# Power_Board_DRV8323.net
KiCad netlist of a schematic drawn in Altium Designer
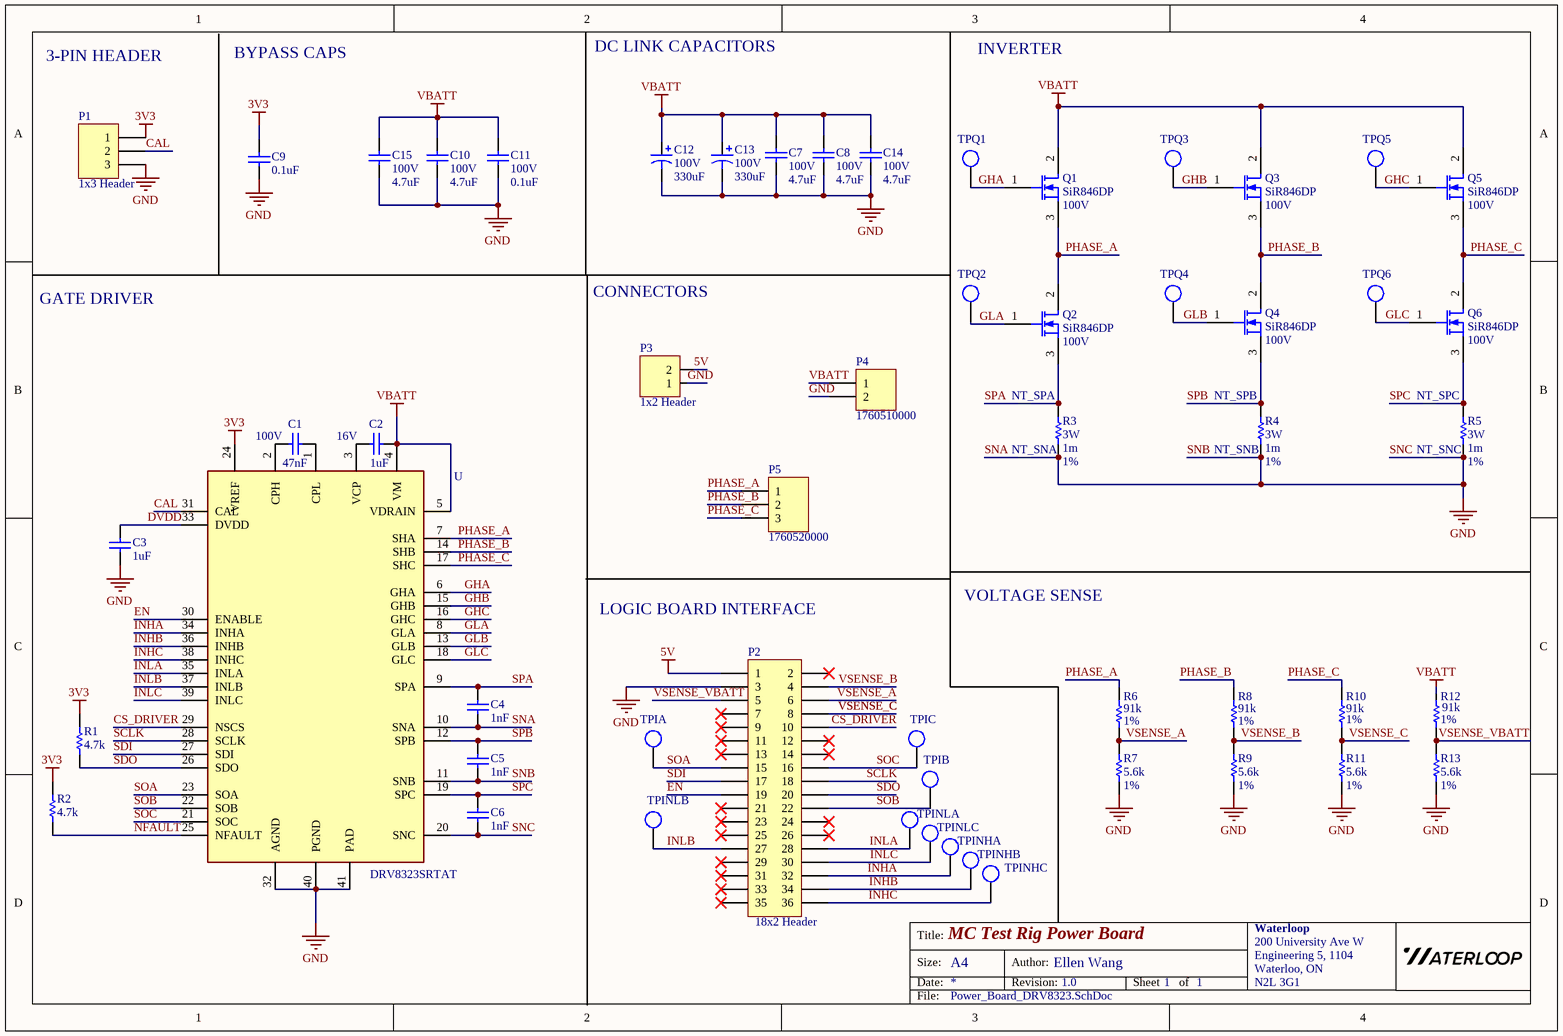
[diagram p0: Power_Board_DRV8323.SchDoc]

(export (version "E")
  (design (tool "Eeschema 10.0.6"))
  (components
    (comp (ref "C1")
      (value "47nF")
      (footprint "0805 - Capacitor")
      (description "Nonpolarized Capacitor")
      (fields
        (field (name "MANUFACTURER") "YAGEO")
        (field (name "RATING") "100V")
        (field (name "MANUFACTURER PART NUMBER") "CC0805KKX7R0BB473")
      )
      (libsource (lib "General") (part "Capacitor - Nonpolarized"))
    )
    (comp (ref "C2")
      (value "1uF")
      (footprint "0805 - Capacitor")
      (description "Nonpolarized Capacitor")
      (fields
        (field (name "MANUFACTURER") "YAGEO")
        (field (name "RATING") "16V")
        (field (name "MANUFACTURER PART NUMBER") "CC0805KKX7R7BB105")
      )
      (libsource (lib "General") (part "Capacitor - Nonpolarized"))
    )
    (comp (ref "C3")
      (value "1uF")
      (footprint "0805 - Capacitor")
      (description "Nonpolarized Capacitor")
      (fields
        (field (name "MANUFACTURER") "YAGEO")
        (field (name "MANUFACTURER PART NUMBER") "CC0805KKX7R7BB105")
      )
      (libsource (lib "General") (part "Capacitor - Nonpolarized"))
    )
    (comp (ref "C4")
      (value "1nF")
      (footprint "0805 - Capacitor")
      (description "Nonpolarized Capacitor")
      (fields
        (field (name "MANUFACTURER") "YAGEO")
        (field (name "MANUFACTURER PART NUMBER") "CC0805KRX7R0BB102")
      )
      (libsource (lib "General") (part "Capacitor - Nonpolarized"))
    )
    (comp (ref "C5")
      (value "1nF")
      (footprint "0805 - Capacitor")
      (description "Nonpolarized Capacitor")
      (fields
        (field (name "MANUFACTURER") "YAGEO")
        (field (name "MANUFACTURER PART NUMBER") "CC0805KRX7R0BB102")
      )
      (libsource (lib "General") (part "Capacitor - Nonpolarized"))
    )
    (comp (ref "C6")
      (value "1nF")
      (footprint "0805 - Capacitor")
      (description "Nonpolarized Capacitor")
      (fields
        (field (name "MANUFACTURER") "YAGEO")
        (field (name "MANUFACTURER PART NUMBER") "CC0805KRX7R0BB102")
      )
      (libsource (lib "General") (part "Capacitor - Nonpolarized"))
    )
    (comp (ref "C7")
      (value "4.7uF")
      (footprint "1210 - Capacitor")
      (description "Nonpolarized Capacitor")
      (fields
        (field (name "MANUFACTURER") "Holy Stone Enterprise Co., Ltd.")
        (field (name "RATING") "100V")
        (field (name "MANUFACTURER PART NUMBER") "C1210X475K101T")
      )
      (libsource (lib "General") (part "Capacitor - Nonpolarized"))
    )
    (comp (ref "C8")
      (value "4.7uF")
      (footprint "1210 - Capacitor")
      (description "Nonpolarized Capacitor")
      (fields
        (field (name "MANUFACTURER") "Holy Stone Enterprise Co., Ltd.")
        (field (name "RATING") "100V")
        (field (name "MANUFACTURER PART NUMBER") "C1210X475K101T")
      )
      (libsource (lib "") (part "Capacitor - Nonpolarized_2"))
    )
    (comp (ref "C9")
      (value "0.1uF")
      (footprint "0805 - Capacitor")
      (description "Nonpolarized Capacitor")
      (fields
        (field (name "MANUFACTURER") "Samsung Electro-Mechanics")
        (field (name "MANUFACTURER PART NUMBER") "CL21B104KCFWPNE")
      )
      (libsource (lib "") (part "Capacitor - Nonpolarized_1"))
    )
    (comp (ref "C10")
      (value "4.7uF")
      (footprint "1210 - Capacitor")
      (description "Nonpolarized Capacitor")
      (fields
        (field (name "MANUFACTURER") "Holy Stone Enterprise Co., Ltd.")
        (field (name "RATING") "100V")
        (field (name "MANUFACTURER PART NUMBER") "C1210X475K101T")
      )
      (libsource (lib "") (part "Capacitor - Nonpolarized_2"))
    )
    (comp (ref "C11")
      (value "0.1uF")
      (footprint "0805 - Capacitor")
      (description "Nonpolarized Capacitor")
      (fields
        (field (name "MANUFACTURER") "Samsung Electro-Mechanics")
        (field (name "RATING") "100V")
        (field (name "MANUFACTURER PART NUMBER") "CL21B104KCFWPNE")
      )
      (libsource (lib "") (part "Capacitor - Nonpolarized_2"))
    )
    (comp (ref "C12")
      (value "330uF")
      (footprint "OCVZ0606 - CAPACITOR")
      (description "Polarized Capacitor")
      (fields
        (field (name "RATING") "100V")
        (field (name "MANUFACTURER") "Panasonic Electronic Components")
        (field (name "MANUFACTURER PART NUMBER") "EEE-FK2A331AM")
      )
      (libsource (lib "General") (part "Capacitor - Polarized"))
    )
    (comp (ref "C13")
      (value "330uF")
      (footprint "OCVZ0606 - CAPACITOR")
      (description "Polarized Capacitor")
      (fields
        (field (name "RATING") "100V")
        (field (name "MANUFACTURER") "Panasonic Electronic Components")
        (field (name "MANUFACTURER PART NUMBER") "EEE-FK2A331AM")
      )
      (libsource (lib "General") (part "Capacitor - Polarized"))
    )
    (comp (ref "C14")
      (value "4.7uF")
      (footprint "1210 - Capacitor")
      (description "Nonpolarized Capacitor")
      (fields
        (field (name "MANUFACTURER") "Holy Stone Enterprise Co., Ltd.")
        (field (name "RATING") "100V")
        (field (name "MANUFACTURER PART NUMBER") "C1210X475K101T")
      )
      (libsource (lib "") (part "Capacitor - Nonpolarized_2"))
    )
    (comp (ref "C15")
      (value "4.7uF")
      (footprint "1210 - Capacitor")
      (description "Nonpolarized Capacitor")
      (fields
        (field (name "MANUFACTURER") "Holy Stone Enterprise Co., Ltd.")
        (field (name "RATING") "100V")
        (field (name "MANUFACTURER PART NUMBER") "C1210X475K101T")
      )
      (libsource (lib "") (part "Capacitor - Nonpolarized_2"))
    )
    (comp (ref "NT_SNA") (value "NetTie") (footprint "Net Tie") (libsource (lib "General") (part "Net Tie")))
    (comp (ref "NT_SNB") (value "NetTie") (footprint "Net Tie") (libsource (lib "General") (part "Net Tie")))
    (comp (ref "NT_SNC") (value "NetTie") (footprint "Net Tie") (libsource (lib "General") (part "Net Tie")))
    (comp (ref "NT_SPA") (value "NetTie") (footprint "Net Tie") (libsource (lib "General") (part "Net Tie")))
    (comp (ref "NT_SPB") (value "NetTie") (footprint "Net Tie") (libsource (lib "General") (part "Net Tie")))
    (comp (ref "NT_SPC") (value "NetTie") (footprint "Net Tie") (libsource (lib "General") (part "Net Tie")))
    (comp (ref "P1")
      (value "1x3 Header")
      (footprint "HDR1X3")
      (description "1x3 Pin Header")
      (libsource (lib "GeneralConnectors") (part "1x3 Header"))
    )
    (comp (ref "P2")
      (value "Header 18X2")
      (footprint "HDR2X18")
      (description "Header, 18-Pin, Dual row")
      (fields (field (name "PUBLISHER") "Altium Limited"))
      (libsource (lib "Miscellaneous Connectors") (part "Header 18X2"))
    )
    (comp (ref "P3")
      (value "1x2 Header")
      (footprint "HDR1X2")
      (description "1x2 Pin Header")
      (libsource (lib "GeneralConnectors") (part "1x2 Header"))
    )
    (comp (ref "P4")
      (value "1760510000")
      (footprint "1760510000")
      (description "1x2 Screw Terminal Block")
      (fields
        (field (name "MANUFACTURER PART NUMBER") "OSTTC022162")
        (field (name "MANUFACTURER") "On Shore Technology Inc.")
      )
      (libsource (lib "GeneralConnectors") (part "1760510000"))
    )
    (comp (ref "P5")
      (value "1760520000")
      (footprint "1760520000")
      (description "1x3 Screw Terminal Block")
      (fields
        (field (name "MANUFACTURER PART NUMBER") "282857-3")
        (field (name "MANUFACTURER") "TE Connectivity AMP Connectors")
      )
      (libsource (lib "GeneralConnectors") (part "1760520000"))
    )
    (comp (ref "Q1")
      (value "MOSFET-N")
      (footprint "PowerPAK® SO-8")
      (description "N-Channel MOSFET")
      (fields (field (name "SUPPLIER PART NUMBER") "SiR846DP") (field (name "RATING") "100V"))
      (libsource (lib "General") (part "MOSFET-N"))
    )
    (comp (ref "Q2")
      (value "MOSFET-N")
      (footprint "PowerPAK® SO-8")
      (description "N-Channel MOSFET")
      (fields (field (name "SUPPLIER PART NUMBER") "SiR846DP") (field (name "RATING") "100V"))
      (libsource (lib "General") (part "MOSFET-N"))
    )
    (comp (ref "Q3")
      (value "MOSFET-N")
      (footprint "PowerPAK® SO-8")
      (description "N-Channel MOSFET")
      (fields (field (name "SUPPLIER PART NUMBER") "SiR846DP") (field (name "RATING") "100V"))
      (libsource (lib "General") (part "MOSFET-N"))
    )
    (comp (ref "Q4")
      (value "MOSFET-N")
      (footprint "PowerPAK® SO-8")
      (description "N-Channel MOSFET")
      (fields (field (name "SUPPLIER PART NUMBER") "SiR846DP") (field (name "RATING") "100V"))
      (libsource (lib "General") (part "MOSFET-N"))
    )
    (comp (ref "Q5")
      (value "MOSFET-N")
      (footprint "PowerPAK® SO-8")
      (description "N-Channel MOSFET")
      (fields (field (name "SUPPLIER PART NUMBER") "SiR846DP") (field (name "RATING") "100V"))
      (libsource (lib "General") (part "MOSFET-N"))
    )
    (comp (ref "Q6")
      (value "MOSFET-N")
      (footprint "PowerPAK® SO-8")
      (description "N-Channel MOSFET")
      (fields (field (name "SUPPLIER PART NUMBER") "SiR846DP") (field (name "RATING") "100V"))
      (libsource (lib "General") (part "MOSFET-N"))
    )
    (comp (ref "R1")
      (value "4.7k")
      (footprint "0603 - Resistor")
      (description "Resistor")
      (fields
        (field (name "MANUFACTURER PART NUMBER") "RC0603FR-074K7L")
        (field (name "MANUFACTURER") "YAGEO")
      )
      (libsource (lib "General") (part "Resistor"))
    )
    (comp (ref "R2")
      (value "4.7k")
      (footprint "0603 - Resistor")
      (description "Resistor")
      (fields
        (field (name "MANUFACTURER PART NUMBER") "RC0603FR-074K7L")
        (field (name "MANUFACTURER") "YAGEO")
      )
      (libsource (lib "General") (part "Resistor"))
    )
    (comp (ref "R3")
      (value "1m")
      (footprint "2512 - RESISTOR")
      (description "Resistor")
      (fields
        (field (name "RATING") "3W")
        (field (name "MANUFACTURER PART NUMBER") "CSR2512C0R001F")
        (field (name "MANUFACTURER") "Riedon")
        (field (name "TOLERANCE") "1%")
      )
      (libsource (lib "General") (part "Resistor"))
    )
    (comp (ref "R4")
      (value "1m")
      (footprint "2512 - RESISTOR")
      (description "Resistor")
      (fields
        (field (name "RATING") "3W")
        (field (name "MANUFACTURER PART NUMBER") "CSR2512C0R001F")
        (field (name "MANUFACTURER") "Riedon")
        (field (name "TOLERANCE") "1%")
      )
      (libsource (lib "General") (part "Resistor"))
    )
    (comp (ref "R5")
      (value "1m")
      (footprint "2512 - RESISTOR")
      (description "Resistor")
      (fields
        (field (name "RATING") "3W")
        (field (name "MANUFACTURER PART NUMBER") "CSR2512C0R001F")
        (field (name "MANUFACTURER") "Riedon")
        (field (name "TOLERANCE") "1%")
      )
      (libsource (lib "General") (part "Resistor"))
    )
    (comp (ref "R6")
      (value "91k")
      (footprint "0603 - Resistor")
      (description "Resistor")
      (fields
        (field (name "MANUFACTURER PART NUMBER") "RC0603FR-0791KL")
        (field (name "MANUFACTURER") "YAGEO")
        (field (name "TOLERANCE") "1%")
      )
      (libsource (lib "General") (part "Resistor"))
    )
    (comp (ref "R7")
      (value "5.6k")
      (footprint "0603 - Resistor")
      (description "Resistor")
      (fields
        (field (name "MANUFACTURER PART NUMBER") "RC0603FR-075K6L")
        (field (name "MANUFACTURER") "YAGEO")
        (field (name "TOLERANCE") "1%")
      )
      (libsource (lib "General") (part "Resistor"))
    )
    (comp (ref "R8")
      (value "91k")
      (footprint "0603 - Resistor")
      (description "Resistor")
      (fields
        (field (name "MANUFACTURER PART NUMBER") "RC0603FR-0791KL")
        (field (name "MANUFACTURER") "YAGEO")
        (field (name "TOLERANCE") "1%")
      )
      (libsource (lib "General") (part "Resistor"))
    )
    (comp (ref "R9")
      (value "5.6k")
      (footprint "0603 - Resistor")
      (description "Resistor")
      (fields
        (field (name "MANUFACTURER PART NUMBER") "RC0603FR-075K6L")
        (field (name "MANUFACTURER") "YAGEO")
        (field (name "TOLERANCE") "1%")
      )
      (libsource (lib "General") (part "Resistor"))
    )
    (comp (ref "R10")
      (value "91k")
      (footprint "0603 - Resistor")
      (description "Resistor")
      (fields
        (field (name "MANUFACTURER PART NUMBER") "RC0603FR-0791KL")
        (field (name "MANUFACTURER") "YAGEO")
        (field (name "TOLERANCE") "1%")
      )
      (libsource (lib "General") (part "Resistor"))
    )
    (comp (ref "R11")
      (value "5.6k")
      (footprint "0603 - Resistor")
      (description "Resistor")
      (fields
        (field (name "MANUFACTURER PART NUMBER") "RC0603FR-075K6L")
        (field (name "MANUFACTURER") "YAGEO")
        (field (name "TOLERANCE") "1%")
      )
      (libsource (lib "General") (part "Resistor"))
    )
    (comp (ref "R12")
      (value "91k")
      (footprint "0603 - Resistor")
      (description "Resistor")
      (fields
        (field (name "MANUFACTURER PART NUMBER") "RC0603FR-0791KL")
        (field (name "MANUFACTURER") "YAGEO")
        (field (name "TOLERANCE") "1%")
      )
      (libsource (lib "General") (part "Resistor"))
    )
    (comp (ref "R13")
      (value "5.6k")
      (footprint "0603 - Resistor")
      (description "Resistor")
      (fields
        (field (name "MANUFACTURER PART NUMBER") "RC0603FR-075K6L")
        (field (name "MANUFACTURER") "YAGEO")
        (field (name "TOLERANCE") "1%")
      )
      (libsource (lib "General") (part "Resistor"))
    )
    (comp (ref "TPIA")
      (value "Test Point")
      (footprint "Test Point")
      (libsource (lib "General") (part "Test Point"))
    )
    (comp (ref "TPIB")
      (value "Test Point")
      (footprint "Test Point")
      (libsource (lib "General") (part "Test Point"))
    )
    (comp (ref "TPIC")
      (value "Test Point")
      (footprint "Test Point")
      (libsource (lib "General") (part "Test Point"))
    )
    (comp (ref "TPINHA")
      (value "Test Point")
      (footprint "Test Point")
      (libsource (lib "General") (part "Test Point"))
    )
    (comp (ref "TPINHB")
      (value "Test Point")
      (footprint "Test Point")
      (libsource (lib "General") (part "Test Point"))
    )
    (comp (ref "TPINHC")
      (value "Test Point")
      (footprint "Test Point")
      (libsource (lib "General") (part "Test Point"))
    )
    (comp (ref "TPINLA")
      (value "Test Point")
      (footprint "Test Point")
      (libsource (lib "General") (part "Test Point"))
    )
    (comp (ref "TPINLB")
      (value "Test Point")
      (footprint "Test Point")
      (libsource (lib "General") (part "Test Point"))
    )
    (comp (ref "TPINLC")
      (value "Test Point")
      (footprint "Test Point")
      (libsource (lib "General") (part "Test Point"))
    )
    (comp (ref "TPQ1")
      (value "Test Point")
      (footprint "Test Point")
      (libsource (lib "General") (part "Test Point"))
    )
    (comp (ref "TPQ2")
      (value "Test Point")
      (footprint "Test Point")
      (libsource (lib "General") (part "Test Point"))
    )
    (comp (ref "TPQ3")
      (value "Test Point")
      (footprint "Test Point")
      (libsource (lib "General") (part "Test Point"))
    )
    (comp (ref "TPQ4")
      (value "Test Point")
      (footprint "Test Point")
      (libsource (lib "General") (part "Test Point"))
    )
    (comp (ref "TPQ5")
      (value "Test Point")
      (footprint "Test Point")
      (libsource (lib "General") (part "Test Point"))
    )
    (comp (ref "TPQ6")
      (value "Test Point")
      (footprint "Test Point")
      (libsource (lib "General") (part "Test Point"))
    )
    (comp (ref "U")
      (value "DRV8323SRTAT")
      (footprint "DRV8323SRTAT")
      (description "Multiphase Motor Driver Power MOSFET SPI")
      (fields (field (name "MANUFACTURER") "Texas Instruments"))
      (libsource (lib "MC") (part "DRV8323SRTAT"))
    )
  )
  (nets
    (net (code "1") (name "/CAL") (class "Default")
      (node (ref "P1") (pin "2") (pinfunction "2_2") (pintype "passive"))
      (node (ref "U") (pin "31") (pinfunction "CAL_31") (pintype "passive"))
    )
    (net (code "2") (name "/CS_DRIVER") (class "Default")
      (node (ref "P2") (pin "10") (pinfunction "10_10") (pintype "passive"))
      (node (ref "U") (pin "29") (pinfunction "NSCS_29") (pintype "passive"))
    )
    (net (code "3") (name "/DVDD") (class "Default")
      (node (ref "C3") (pin "2") (pinfunction "2_2") (pintype "passive"))
      (node (ref "U") (pin "33") (pinfunction "DVDD_33") (pintype "power_in"))
    )
    (net (code "4") (name "/EN") (class "Default")
      (node (ref "P2") (pin "19") (pinfunction "19_19") (pintype "passive"))
      (node (ref "U") (pin "30") (pinfunction "ENABLE_30") (pintype "passive"))
    )
    (net (code "5") (name "/GHA") (class "Default")
      (node (ref "Q1") (pin "1") (pinfunction "G_1") (pintype "passive"))
      (node (ref "TPQ1") (pin "1") (pinfunction "0_1") (pintype "passive"))
      (node (ref "U") (pin "6") (pinfunction "GHA_6") (pintype "passive"))
    )
    (net (code "6") (name "/GHB") (class "Default")
      (node (ref "Q3") (pin "1") (pinfunction "G_1") (pintype "passive"))
      (node (ref "TPQ3") (pin "1") (pinfunction "0_1") (pintype "passive"))
      (node (ref "U") (pin "15") (pinfunction "GHB_15") (pintype "passive"))
    )
    (net (code "7") (name "/GHC") (class "Default")
      (node (ref "Q5") (pin "1") (pinfunction "G_1") (pintype "passive"))
      (node (ref "TPQ5") (pin "1") (pinfunction "0_1") (pintype "passive"))
      (node (ref "U") (pin "16") (pinfunction "GHC_16") (pintype "passive"))
    )
    (net (code "8") (name "/GLA") (class "Default")
      (node (ref "Q2") (pin "1") (pinfunction "G_1") (pintype "passive"))
      (node (ref "TPQ2") (pin "1") (pinfunction "0_1") (pintype "passive"))
      (node (ref "U") (pin "8") (pinfunction "GLA_8") (pintype "passive"))
    )
    (net (code "9") (name "/GLB") (class "Default")
      (node (ref "Q4") (pin "1") (pinfunction "G_1") (pintype "passive"))
      (node (ref "TPQ4") (pin "1") (pinfunction "0_1") (pintype "passive"))
      (node (ref "U") (pin "13") (pinfunction "GLB_13") (pintype "passive"))
    )
    (net (code "10") (name "/GLC") (class "Default")
      (node (ref "Q6") (pin "1") (pinfunction "G_1") (pintype "passive"))
      (node (ref "TPQ6") (pin "1") (pinfunction "0_1") (pintype "passive"))
      (node (ref "U") (pin "18") (pinfunction "GLC_18") (pintype "passive"))
    )
    (net (code "11") (name "/INHA") (class "Default")
      (node (ref "P2") (pin "32") (pinfunction "32_32") (pintype "passive"))
      (node (ref "TPINHA") (pin "1") (pinfunction "0_1") (pintype "passive"))
      (node (ref "U") (pin "34") (pinfunction "INHA_34") (pintype "passive"))
    )
    (net (code "12") (name "/INHB") (class "Default")
      (node (ref "P2") (pin "34") (pinfunction "34_34") (pintype "passive"))
      (node (ref "TPINHB") (pin "1") (pinfunction "0_1") (pintype "passive"))
      (node (ref "U") (pin "36") (pinfunction "INHB_36") (pintype "passive"))
    )
    (net (code "13") (name "/INHC") (class "Default")
      (node (ref "P2") (pin "36") (pinfunction "36_36") (pintype "passive"))
      (node (ref "TPINHC") (pin "1") (pinfunction "0_1") (pintype "passive"))
      (node (ref "U") (pin "38") (pinfunction "INHC_38") (pintype "passive"))
    )
    (net (code "14") (name "/INLA") (class "Default")
      (node (ref "P2") (pin "28") (pinfunction "28_28") (pintype "passive"))
      (node (ref "TPINLA") (pin "1") (pinfunction "0_1") (pintype "passive"))
      (node (ref "U") (pin "35") (pinfunction "INLA_35") (pintype "passive"))
    )
    (net (code "15") (name "/INLB") (class "Default")
      (node (ref "P2") (pin "27") (pinfunction "27_27") (pintype "passive"))
      (node (ref "TPINLB") (pin "1") (pinfunction "0_1") (pintype "passive"))
      (node (ref "U") (pin "37") (pinfunction "INLB_37") (pintype "passive"))
    )
    (net (code "16") (name "/INLC") (class "Default")
      (node (ref "P2") (pin "30") (pinfunction "30_30") (pintype "passive"))
      (node (ref "TPINLC") (pin "1") (pinfunction "0_1") (pintype "passive"))
      (node (ref "U") (pin "39") (pinfunction "INLC_39") (pintype "passive"))
    )
    (net (code "17") (name "/NFAULT") (class "Default")
      (node (ref "R2") (pin "1") (pinfunction "1_1") (pintype "passive"))
      (node (ref "U") (pin "25") (pinfunction "NFAULT_25") (pintype "passive"))
    )
    (net (code "18") (name "/PHASE_A") (class "Default")
      (node (ref "P5") (pin "1") (pinfunction "1_1") (pintype "passive"))
      (node (ref "Q1") (pin "3") (pinfunction "S_3") (pintype "passive"))
      (node (ref "Q2") (pin "2") (pinfunction "D_2") (pintype "passive"))
      (node (ref "R6") (pin "1") (pinfunction "1_1") (pintype "passive"))
      (node (ref "U") (pin "7") (pinfunction "SHA_7") (pintype "passive"))
    )
    (net (code "19") (name "/PHASE_B") (class "Default")
      (node (ref "P5") (pin "2") (pinfunction "2_2") (pintype "passive"))
      (node (ref "Q3") (pin "3") (pinfunction "S_3") (pintype "passive"))
      (node (ref "Q4") (pin "2") (pinfunction "D_2") (pintype "passive"))
      (node (ref "R8") (pin "1") (pinfunction "1_1") (pintype "passive"))
      (node (ref "U") (pin "14") (pinfunction "SHB_14") (pintype "passive"))
    )
    (net (code "20") (name "/PHASE_C") (class "Default")
      (node (ref "P5") (pin "3") (pinfunction "3_3") (pintype "passive"))
      (node (ref "Q5") (pin "3") (pinfunction "S_3") (pintype "passive"))
      (node (ref "Q6") (pin "2") (pinfunction "D_2") (pintype "passive"))
      (node (ref "R10") (pin "1") (pinfunction "1_1") (pintype "passive"))
      (node (ref "U") (pin "17") (pinfunction "SHC_17") (pintype "passive"))
    )
    (net (code "21") (name "/SCLK") (class "Default")
      (node (ref "P2") (pin "18") (pinfunction "18_18") (pintype "passive"))
      (node (ref "U") (pin "28") (pinfunction "SCLK_28") (pintype "passive"))
    )
    (net (code "22") (name "/SDI") (class "Default")
      (node (ref "P2") (pin "17") (pinfunction "17_17") (pintype "passive"))
      (node (ref "U") (pin "27") (pinfunction "SDI_27") (pintype "passive"))
    )
    (net (code "23") (name "/SDO") (class "Default")
      (node (ref "P2") (pin "20") (pinfunction "20_20") (pintype "passive"))
      (node (ref "R1") (pin "1") (pinfunction "1_1") (pintype "passive"))
      (node (ref "U") (pin "26") (pinfunction "SDO_26") (pintype "passive"))
    )
    (net (code "24") (name "/SNA") (class "Default")
      (node (ref "C4") (pin "1") (pinfunction "1_1") (pintype "passive"))
      (node (ref "NT_SNA") (pin "1") (pinfunction "1_1") (pintype "passive"))
      (node (ref "U") (pin "10") (pinfunction "SNA_10") (pintype "passive"))
    )
    (net (code "25") (name "/SNB") (class "Default")
      (node (ref "C5") (pin "1") (pinfunction "1_1") (pintype "passive"))
      (node (ref "NT_SNB") (pin "1") (pinfunction "1_1") (pintype "passive"))
      (node (ref "U") (pin "11") (pinfunction "SNB_11") (pintype "passive"))
    )
    (net (code "26") (name "/SNC") (class "Default")
      (node (ref "C6") (pin "1") (pinfunction "1_1") (pintype "passive"))
      (node (ref "NT_SNC") (pin "1") (pinfunction "1_1") (pintype "passive"))
      (node (ref "U") (pin "20") (pinfunction "SNC_20") (pintype "passive"))
    )
    (net (code "27") (name "/SOA") (class "Default")
      (node (ref "P2") (pin "15") (pinfunction "15_15") (pintype "passive"))
      (node (ref "TPIA") (pin "1") (pinfunction "0_1") (pintype "passive"))
      (node (ref "U") (pin "23") (pinfunction "SOA_23") (pintype "passive"))
    )
    (net (code "28") (name "/SOB") (class "Default")
      (node (ref "P2") (pin "22") (pinfunction "22_22") (pintype "passive"))
      (node (ref "TPIB") (pin "1") (pinfunction "0_1") (pintype "passive"))
      (node (ref "U") (pin "22") (pinfunction "SOB_22") (pintype "passive"))
    )
    (net (code "29") (name "/SOC") (class "Default")
      (node (ref "P2") (pin "16") (pinfunction "16_16") (pintype "passive"))
      (node (ref "TPIC") (pin "1") (pinfunction "0_1") (pintype "passive"))
      (node (ref "U") (pin "21") (pinfunction "SOC_21") (pintype "passive"))
    )
    (net (code "30") (name "/SPA") (class "Default")
      (node (ref "C4") (pin "2") (pinfunction "2_2") (pintype "passive"))
      (node (ref "NT_SPA") (pin "1") (pinfunction "1_1") (pintype "passive"))
      (node (ref "U") (pin "9") (pinfunction "SPA_9") (pintype "passive"))
    )
    (net (code "31") (name "/SPB") (class "Default")
      (node (ref "C5") (pin "2") (pinfunction "2_2") (pintype "passive"))
      (node (ref "NT_SPB") (pin "1") (pinfunction "1_1") (pintype "passive"))
      (node (ref "U") (pin "12") (pinfunction "SPB_12") (pintype "passive"))
    )
    (net (code "32") (name "/SPC") (class "Default")
      (node (ref "C6") (pin "2") (pinfunction "2_2") (pintype "passive"))
      (node (ref "NT_SPC") (pin "1") (pinfunction "1_1") (pintype "passive"))
      (node (ref "U") (pin "19") (pinfunction "SPC_19") (pintype "passive"))
    )
    (net (code "33") (name "/VSENSE_A") (class "Default")
      (node (ref "P2") (pin "6") (pinfunction "6_6") (pintype "passive"))
      (node (ref "R6") (pin "2") (pinfunction "2_2") (pintype "passive"))
      (node (ref "R7") (pin "1") (pinfunction "1_1") (pintype "passive"))
    )
    (net (code "34") (name "/VSENSE_B") (class "Default")
      (node (ref "P2") (pin "4") (pinfunction "4_4") (pintype "passive"))
      (node (ref "R8") (pin "2") (pinfunction "2_2") (pintype "passive"))
      (node (ref "R9") (pin "1") (pinfunction "1_1") (pintype "passive"))
    )
    (net (code "35") (name "/VSENSE_C") (class "Default")
      (node (ref "P2") (pin "8") (pinfunction "8_8") (pintype "passive"))
      (node (ref "R10") (pin "2") (pinfunction "2_2") (pintype "passive"))
      (node (ref "R11") (pin "1") (pinfunction "1_1") (pintype "passive"))
    )
    (net (code "36") (name "/VSENSE_VBATT") (class "Default")
      (node (ref "P2") (pin "5") (pinfunction "5_5") (pintype "passive"))
      (node (ref "R12") (pin "2") (pinfunction "2_2") (pintype "passive"))
      (node (ref "R13") (pin "1") (pinfunction "1_1") (pintype "passive"))
    )
    (net (code "37") (name "3V3") (class "Default")
      (node (ref "C9") (pin "1") (pinfunction "1_1") (pintype "passive"))
      (node (ref "P1") (pin "1") (pinfunction "1_1") (pintype "passive"))
      (node (ref "R1") (pin "2") (pinfunction "2_2") (pintype "passive"))
      (node (ref "R2") (pin "2") (pinfunction "2_2") (pintype "passive"))
      (node (ref "U") (pin "24") (pinfunction "VREF_24") (pintype "power_in"))
    )
    (net (code "38") (name "5V") (class "Default")
      (node (ref "P2") (pin "1") (pinfunction "1_1") (pintype "passive"))
      (node (ref "P3") (pin "2") (pinfunction "2_2") (pintype "passive"))
    )
    (net (code "39") (name "GND") (class "Default")
      (node (ref "C10") (pin "2") (pinfunction "2_2") (pintype "passive"))
      (node (ref "C11") (pin "2") (pinfunction "2_2") (pintype "passive"))
      (node (ref "C12") (pin "2") (pinfunction "2_2") (pintype "passive"))
      (node (ref "C13") (pin "2") (pinfunction "2_2") (pintype "passive"))
      (node (ref "C14") (pin "2") (pinfunction "2_2") (pintype "passive"))
      (node (ref "C15") (pin "2") (pinfunction "2_2") (pintype "passive"))
      (node (ref "C3") (pin "1") (pinfunction "1_1") (pintype "passive"))
      (node (ref "C7") (pin "2") (pinfunction "2_2") (pintype "passive"))
      (node (ref "C8") (pin "2") (pinfunction "2_2") (pintype "passive"))
      (node (ref "C9") (pin "2") (pinfunction "2_2") (pintype "passive"))
      (node (ref "NT_SNA") (pin "2") (pinfunction "2_2") (pintype "passive"))
      (node (ref "NT_SNB") (pin "2") (pinfunction "2_2") (pintype "passive"))
      (node (ref "NT_SNC") (pin "2") (pinfunction "2_2") (pintype "passive"))
      (node (ref "P1") (pin "3") (pinfunction "3_3") (pintype "passive"))
      (node (ref "P2") (pin "3") (pinfunction "3_3") (pintype "passive"))
      (node (ref "P3") (pin "1") (pinfunction "1_1") (pintype "passive"))
      (node (ref "P4") (pin "2") (pinfunction "2_2") (pintype "passive"))
      (node (ref "R11") (pin "2") (pinfunction "2_2") (pintype "passive"))
      (node (ref "R13") (pin "2") (pinfunction "2_2") (pintype "passive"))
      (node (ref "R3") (pin "1") (pinfunction "1_1") (pintype "passive"))
      (node (ref "R4") (pin "1") (pinfunction "1_1") (pintype "passive"))
      (node (ref "R5") (pin "1") (pinfunction "1_1") (pintype "passive"))
      (node (ref "R7") (pin "2") (pinfunction "2_2") (pintype "passive"))
      (node (ref "R9") (pin "2") (pinfunction "2_2") (pintype "passive"))
      (node (ref "U") (pin "32") (pinfunction "AGND_32") (pintype "power_in"))
      (node (ref "U") (pin "40") (pinfunction "PGND_40") (pintype "power_in"))
      (node (ref "U") (pin "41") (pinfunction "PAD_41") (pintype "power_in"))
    )
    (net (code "40") (name "Net-(Q2-S)") (class "Default")
      (node (ref "NT_SPA") (pin "2") (pinfunction "2_2") (pintype "passive"))
      (node (ref "Q2") (pin "3") (pinfunction "S_3") (pintype "passive"))
      (node (ref "R3") (pin "2") (pinfunction "2_2") (pintype "passive"))
    )
    (net (code "41") (name "Net-(Q4-S)") (class "Default")
      (node (ref "NT_SPB") (pin "2") (pinfunction "2_2") (pintype "passive"))
      (node (ref "Q4") (pin "3") (pinfunction "S_3") (pintype "passive"))
      (node (ref "R4") (pin "2") (pinfunction "2_2") (pintype "passive"))
    )
    (net (code "42") (name "Net-(Q6-S)") (class "Default")
      (node (ref "NT_SPC") (pin "2") (pinfunction "2_2") (pintype "passive"))
      (node (ref "Q6") (pin "3") (pinfunction "S_3") (pintype "passive"))
      (node (ref "R5") (pin "2") (pinfunction "2_2") (pintype "passive"))
    )
    (net (code "43") (name "Net-(U-CPH)") (class "Default")
      (node (ref "C1") (pin "1") (pinfunction "1_1") (pintype "passive"))
      (node (ref "U") (pin "2") (pinfunction "CPH_2") (pintype "power_in"))
    )
    (net (code "44") (name "Net-(U-CPL)") (class "Default")
      (node (ref "C1") (pin "2") (pinfunction "2_2") (pintype "passive"))
      (node (ref "U") (pin "1") (pinfunction "CPL_1") (pintype "power_in"))
    )
    (net (code "45") (name "Net-(U-VCP)") (class "Default")
      (node (ref "C2") (pin "1") (pinfunction "1_1") (pintype "passive"))
      (node (ref "U") (pin "3") (pinfunction "VCP_3") (pintype "power_in"))
    )
    (net (code "46") (name "VBATT") (class "Default")
      (node (ref "C10") (pin "2") (pinfunction "2_2") (pintype "passive"))
      (node (ref "C11") (pin "2") (pinfunction "2_2") (pintype "passive"))
      (node (ref "C12") (pin "1") (pinfunction "1_1") (pintype "passive"))
      (node (ref "C13") (pin "1") (pinfunction "1_1") (pintype "passive"))
      (node (ref "C14") (pin "2") (pinfunction "2_2") (pintype "passive"))
      (node (ref "C15") (pin "2") (pinfunction "2_2") (pintype "passive"))
      (node (ref "C2") (pin "2") (pinfunction "2_2") (pintype "passive"))
      (node (ref "C7") (pin "1") (pinfunction "1_1") (pintype "passive"))
      (node (ref "C8") (pin "2") (pinfunction "2_2") (pintype "passive"))
      (node (ref "P4") (pin "1") (pinfunction "1_1") (pintype "passive"))
      (node (ref "Q1") (pin "2") (pinfunction "D_2") (pintype "passive"))
      (node (ref "Q3") (pin "2") (pinfunction "D_2") (pintype "passive"))
      (node (ref "Q5") (pin "2") (pinfunction "D_2") (pintype "passive"))
      (node (ref "R12") (pin "1") (pinfunction "1_1") (pintype "passive"))
      (node (ref "U") (pin "4") (pinfunction "VM_4") (pintype "power_in"))
      (node (ref "U") (pin "5") (pinfunction "VDRAIN_5") (pintype "passive"))
    )
    (net (code "47") (name "unconnected-(P2-Pad2)") (class "Default")
      (node (ref "P2") (pin "2") (pinfunction "2_2") (pintype "passive+no_connect"))
    )
    (net (code "48") (name "unconnected-(P2-Pad7)") (class "Default")
      (node (ref "P2") (pin "7") (pinfunction "7_7") (pintype "passive+no_connect"))
    )
    (net (code "49") (name "unconnected-(P2-Pad9)") (class "Default")
      (node (ref "P2") (pin "9") (pinfunction "9_9") (pintype "passive+no_connect"))
    )
    (net (code "50") (name "unconnected-(P2-Pad11)") (class "Default")
      (node (ref "P2") (pin "11") (pinfunction "11_11") (pintype "passive+no_connect"))
    )
    (net (code "51") (name "unconnected-(P2-Pad12)") (class "Default")
      (node (ref "P2") (pin "12") (pinfunction "12_12") (pintype "passive+no_connect"))
    )
    (net (code "52") (name "unconnected-(P2-Pad13)") (class "Default")
      (node (ref "P2") (pin "13") (pinfunction "13_13") (pintype "passive+no_connect"))
    )
    (net (code "53") (name "unconnected-(P2-Pad14)") (class "Default")
      (node (ref "P2") (pin "14") (pinfunction "14_14") (pintype "passive+no_connect"))
    )
    (net (code "54") (name "unconnected-(P2-Pad21)") (class "Default")
      (node (ref "P2") (pin "21") (pinfunction "21_21") (pintype "passive+no_connect"))
    )
    (net (code "55") (name "unconnected-(P2-Pad23)") (class "Default")
      (node (ref "P2") (pin "23") (pinfunction "23_23") (pintype "passive+no_connect"))
    )
    (net (code "56") (name "unconnected-(P2-Pad24)") (class "Default")
      (node (ref "P2") (pin "24") (pinfunction "24_24") (pintype "passive+no_connect"))
    )
    (net (code "57") (name "unconnected-(P2-Pad25)") (class "Default")
      (node (ref "P2") (pin "25") (pinfunction "25_25") (pintype "passive+no_connect"))
    )
    (net (code "58") (name "unconnected-(P2-Pad26)") (class "Default")
      (node (ref "P2") (pin "26") (pinfunction "26_26") (pintype "passive+no_connect"))
    )
    (net (code "59") (name "unconnected-(P2-Pad29)") (class "Default")
      (node (ref "P2") (pin "29") (pinfunction "29_29") (pintype "passive+no_connect"))
    )
    (net (code "60") (name "unconnected-(P2-Pad31)") (class "Default")
      (node (ref "P2") (pin "31") (pinfunction "31_31") (pintype "passive+no_connect"))
    )
    (net (code "61") (name "unconnected-(P2-Pad33)") (class "Default")
      (node (ref "P2") (pin "33") (pinfunction "33_33") (pintype "passive+no_connect"))
    )
    (net (code "62") (name "unconnected-(P2-Pad35)") (class "Default")
      (node (ref "P2") (pin "35") (pinfunction "35_35") (pintype "passive+no_connect"))
    )
  )
)
